# SAMC21_Xplained_Pro_Level_Converters.net
KiCad netlist of a schematic drawn in Altium Designer
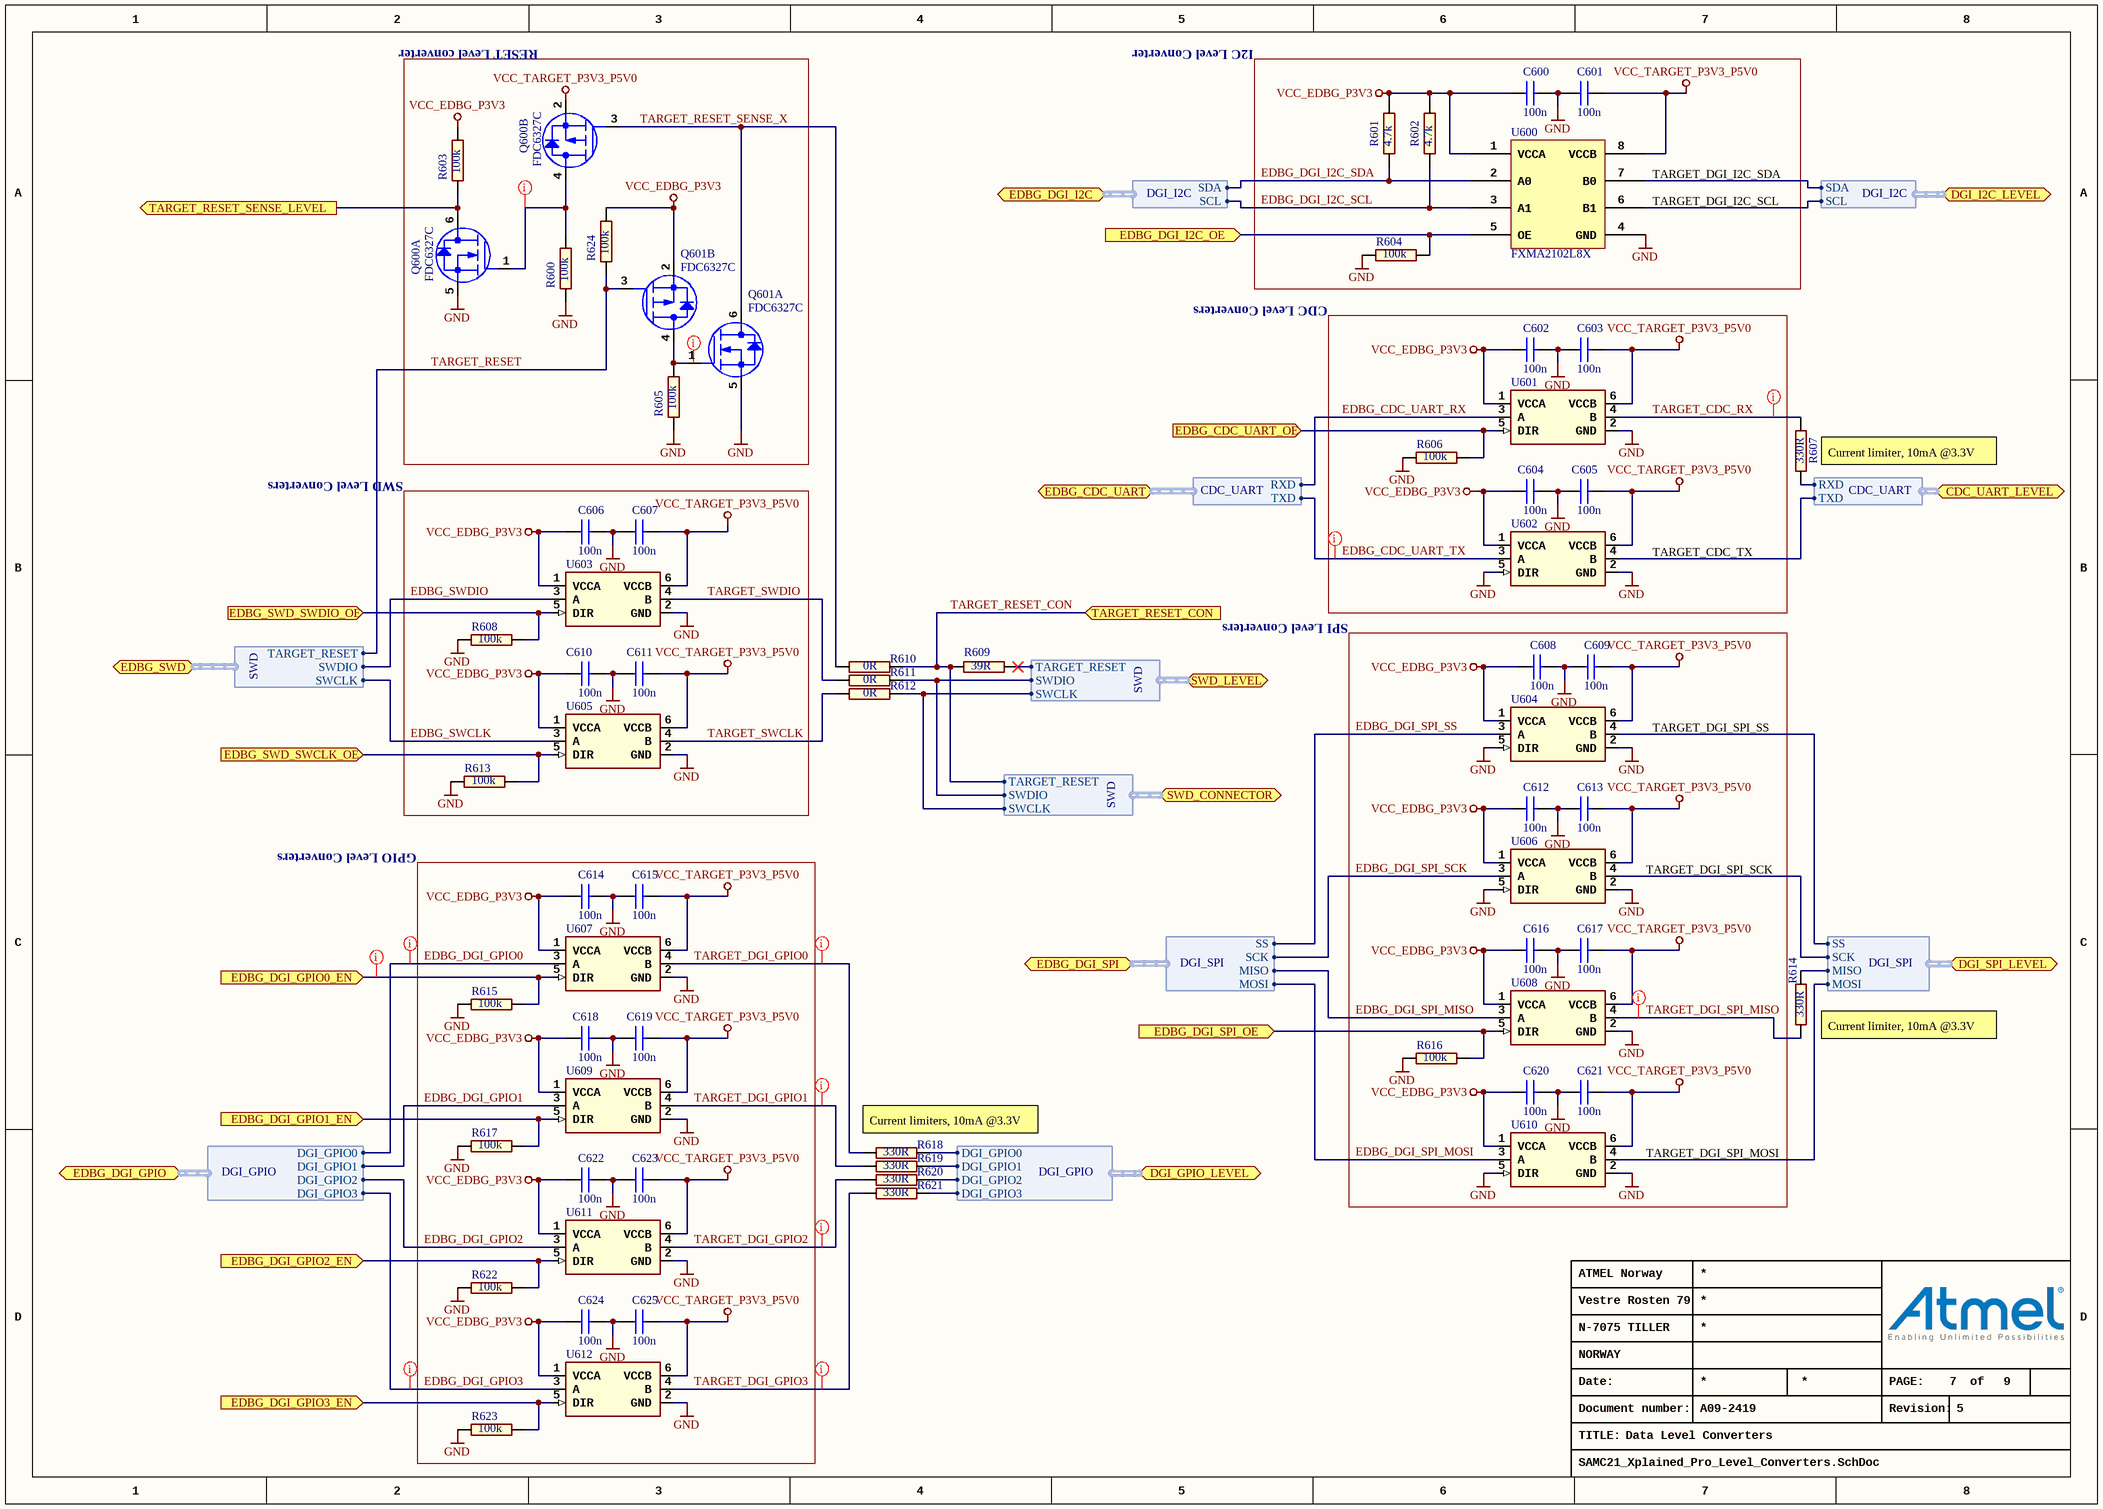
[diagram p0: SAMC21_Xplained_Pro_Level_Converters.SchDoc]

(export (version "E")
  (design (tool "Eeschema 10.0.6"))
  (components
    (comp (ref "C600")
      (value "100n")
      (footprint "AP1-00053")
      (description "Ceramic capacitor, SMD 0402, X7R, 16V, +/-10%")
      (fields (field (name "TOLERANCE") "16V, +/-10%") (field (name "MANUFACTURER") "Kemet"))
      (libsource (lib "AltiumDbLib") (part "CAP-NONPOL"))
    )
    (comp (ref "C601")
      (value "100n")
      (footprint "AP1-00053")
      (description "Ceramic capacitor, SMD 0402, X7R, 16V, +/-10%")
      (fields (field (name "TOLERANCE") "16V, +/-10%") (field (name "MANUFACTURER") "Kemet"))
      (libsource (lib "AltiumDbLib") (part "CAP-NONPOL"))
    )
    (comp (ref "C602")
      (value "100n")
      (footprint "AP1-00053")
      (description "Ceramic capacitor, SMD 0402, X7R, 16V, +/-10%")
      (fields (field (name "TOLERANCE") "16V, +/-10%") (field (name "MANUFACTURER") "Kemet"))
      (libsource (lib "AltiumDbLib") (part "CAP-NONPOL"))
    )
    (comp (ref "C603")
      (value "100n")
      (footprint "AP1-00053")
      (description "Ceramic capacitor, SMD 0402, X7R, 16V, +/-10%")
      (fields (field (name "TOLERANCE") "16V, +/-10%") (field (name "MANUFACTURER") "Kemet"))
      (libsource (lib "AltiumDbLib") (part "CAP-NONPOL"))
    )
    (comp (ref "C604")
      (value "100n")
      (footprint "AP1-00053")
      (description "Ceramic capacitor, SMD 0402, X7R, 16V, +/-10%")
      (fields (field (name "TOLERANCE") "16V, +/-10%") (field (name "MANUFACTURER") "Kemet"))
      (libsource (lib "AltiumDbLib") (part "CAP-NONPOL"))
    )
    (comp (ref "C605")
      (value "100n")
      (footprint "AP1-00053")
      (description "Ceramic capacitor, SMD 0402, X7R, 16V, +/-10%")
      (fields (field (name "TOLERANCE") "16V, +/-10%") (field (name "MANUFACTURER") "Kemet"))
      (libsource (lib "AltiumDbLib") (part "CAP-NONPOL"))
    )
    (comp (ref "C606")
      (value "100n")
      (footprint "AP1-00053")
      (description "Ceramic capacitor, SMD 0402, X7R, 16V, +/-10%")
      (fields (field (name "TOLERANCE") "16V, +/-10%") (field (name "MANUFACTURER") "Kemet"))
      (libsource (lib "AltiumDbLib") (part "CAP-NONPOL"))
    )
    (comp (ref "C607")
      (value "100n")
      (footprint "AP1-00053")
      (description "Ceramic capacitor, SMD 0402, X7R, 16V, +/-10%")
      (fields (field (name "TOLERANCE") "16V, +/-10%") (field (name "MANUFACTURER") "Kemet"))
      (libsource (lib "AltiumDbLib") (part "CAP-NONPOL"))
    )
    (comp (ref "C608")
      (value "100n")
      (footprint "AP1-00053")
      (description "Ceramic capacitor, SMD 0402, X7R, 16V, +/-10%")
      (fields (field (name "TOLERANCE") "16V, +/-10%") (field (name "MANUFACTURER") "Kemet"))
      (libsource (lib "AltiumDbLib") (part "CAP-NONPOL"))
    )
    (comp (ref "C609")
      (value "100n")
      (footprint "AP1-00053")
      (description "Ceramic capacitor, SMD 0402, X7R, 16V, +/-10%")
      (fields (field (name "TOLERANCE") "16V, +/-10%") (field (name "MANUFACTURER") "Kemet"))
      (libsource (lib "AltiumDbLib") (part "CAP-NONPOL"))
    )
    (comp (ref "C610")
      (value "100n")
      (footprint "AP1-00053")
      (description "Ceramic capacitor, SMD 0402, X7R, 16V, +/-10%")
      (fields (field (name "TOLERANCE") "16V, +/-10%") (field (name "MANUFACTURER") "Kemet"))
      (libsource (lib "AltiumDbLib") (part "CAP-NONPOL"))
    )
    (comp (ref "C611")
      (value "100n")
      (footprint "AP1-00053")
      (description "Ceramic capacitor, SMD 0402, X7R, 16V, +/-10%")
      (fields (field (name "TOLERANCE") "16V, +/-10%") (field (name "MANUFACTURER") "Kemet"))
      (libsource (lib "AltiumDbLib") (part "CAP-NONPOL"))
    )
    (comp (ref "C612")
      (value "100n")
      (footprint "AP1-00053")
      (description "Ceramic capacitor, SMD 0402, X7R, 16V, +/-10%")
      (fields (field (name "TOLERANCE") "16V, +/-10%") (field (name "MANUFACTURER") "Kemet"))
      (libsource (lib "AltiumDbLib") (part "CAP-NONPOL"))
    )
    (comp (ref "C613")
      (value "100n")
      (footprint "AP1-00053")
      (description "Ceramic capacitor, SMD 0402, X7R, 16V, +/-10%")
      (fields (field (name "TOLERANCE") "16V, +/-10%") (field (name "MANUFACTURER") "Kemet"))
      (libsource (lib "AltiumDbLib") (part "CAP-NONPOL"))
    )
    (comp (ref "C614")
      (value "100n")
      (footprint "AP1-00053")
      (description "Ceramic capacitor, SMD 0402, X7R, 16V, +/-10%")
      (fields (field (name "TOLERANCE") "16V, +/-10%") (field (name "MANUFACTURER") "Kemet"))
      (libsource (lib "AltiumDbLib") (part "CAP-NONPOL"))
    )
    (comp (ref "C615")
      (value "100n")
      (footprint "AP1-00053")
      (description "Ceramic capacitor, SMD 0402, X7R, 16V, +/-10%")
      (fields (field (name "TOLERANCE") "16V, +/-10%") (field (name "MANUFACTURER") "Kemet"))
      (libsource (lib "AltiumDbLib") (part "CAP-NONPOL"))
    )
    (comp (ref "C616")
      (value "100n")
      (footprint "AP1-00053")
      (description "Ceramic capacitor, SMD 0402, X7R, 16V, +/-10%")
      (fields (field (name "TOLERANCE") "16V, +/-10%") (field (name "MANUFACTURER") "Kemet"))
      (libsource (lib "AltiumDbLib") (part "CAP-NONPOL"))
    )
    (comp (ref "C617")
      (value "100n")
      (footprint "AP1-00053")
      (description "Ceramic capacitor, SMD 0402, X7R, 16V, +/-10%")
      (fields (field (name "TOLERANCE") "16V, +/-10%") (field (name "MANUFACTURER") "Kemet"))
      (libsource (lib "AltiumDbLib") (part "CAP-NONPOL"))
    )
    (comp (ref "C618")
      (value "100n")
      (footprint "AP1-00053")
      (description "Ceramic capacitor, SMD 0402, X7R, 16V, +/-10%")
      (fields (field (name "TOLERANCE") "16V, +/-10%") (field (name "MANUFACTURER") "Kemet"))
      (libsource (lib "AltiumDbLib") (part "CAP-NONPOL"))
    )
    (comp (ref "C619")
      (value "100n")
      (footprint "AP1-00053")
      (description "Ceramic capacitor, SMD 0402, X7R, 16V, +/-10%")
      (fields (field (name "TOLERANCE") "16V, +/-10%") (field (name "MANUFACTURER") "Kemet"))
      (libsource (lib "AltiumDbLib") (part "CAP-NONPOL"))
    )
    (comp (ref "C620")
      (value "100n")
      (footprint "AP1-00053")
      (description "Ceramic capacitor, SMD 0402, X7R, 16V, +/-10%")
      (fields (field (name "TOLERANCE") "16V, +/-10%") (field (name "MANUFACTURER") "Kemet"))
      (libsource (lib "AltiumDbLib") (part "CAP-NONPOL"))
    )
    (comp (ref "C621")
      (value "100n")
      (footprint "AP1-00053")
      (description "Ceramic capacitor, SMD 0402, X7R, 16V, +/-10%")
      (fields (field (name "TOLERANCE") "16V, +/-10%") (field (name "MANUFACTURER") "Kemet"))
      (libsource (lib "AltiumDbLib") (part "CAP-NONPOL"))
    )
    (comp (ref "C622")
      (value "100n")
      (footprint "AP1-00053")
      (description "Ceramic capacitor, SMD 0402, X7R, 16V, +/-10%")
      (fields (field (name "TOLERANCE") "16V, +/-10%") (field (name "MANUFACTURER") "Kemet"))
      (libsource (lib "AltiumDbLib") (part "CAP-NONPOL"))
    )
    (comp (ref "C623")
      (value "100n")
      (footprint "AP1-00053")
      (description "Ceramic capacitor, SMD 0402, X7R, 16V, +/-10%")
      (fields (field (name "TOLERANCE") "16V, +/-10%") (field (name "MANUFACTURER") "Kemet"))
      (libsource (lib "AltiumDbLib") (part "CAP-NONPOL"))
    )
    (comp (ref "C624")
      (value "100n")
      (footprint "AP1-00053")
      (description "Ceramic capacitor, SMD 0402, X7R, 16V, +/-10%")
      (fields (field (name "TOLERANCE") "16V, +/-10%") (field (name "MANUFACTURER") "Kemet"))
      (libsource (lib "AltiumDbLib") (part "CAP-NONPOL"))
    )
    (comp (ref "C625")
      (value "100n")
      (footprint "AP1-00053")
      (description "Ceramic capacitor, SMD 0402, X7R, 16V, +/-10%")
      (fields (field (name "TOLERANCE") "16V, +/-10%") (field (name "MANUFACTURER") "Kemet"))
      (libsource (lib "AltiumDbLib") (part "CAP-NONPOL"))
    )
    (comp (ref "Q600")
      (value "FDC6327C")
      (footprint "AP5-00008")
      (fields (field (name "MANUFACTURER") "Fairchild") (field (name "Comment") "Farnell no: 9844856"))
      (libsource (lib "AltiumDbLib") (part "DUAL_NP_G1S2G2D2S1D1"))
    )
    (comp (ref "Q601")
      (value "FDC6327C")
      (footprint "AP5-00008")
      (fields (field (name "MANUFACTURER") "Fairchild") (field (name "Comment") "Farnell no: 9844856"))
      (libsource (lib "AltiumDbLib") (part "DUAL_NP_G1S2G2D2S1D1"))
    )
    (comp (ref "R600")
      (value "100k")
      (footprint "AP2-00011")
      (description "Thick film resistor, SMD 0402, 1/16W, 1%")
      (fields (field (name "TOLERANCE") "1 %"))
      (libsource (lib "AltiumDbLib") (part "R2"))
    )
    (comp (ref "R601")
      (value "4.7k")
      (footprint "AP2-00011")
      (description "Thick film resistor, SMD 0402, 1/16W, 1%")
      (fields (field (name "TOLERANCE") "1 %"))
      (libsource (lib "AltiumDbLib") (part "R2"))
    )
    (comp (ref "R602")
      (value "4.7k")
      (footprint "AP2-00011")
      (description "Thick film resistor, SMD 0402, 1/16W, 1%")
      (fields (field (name "TOLERANCE") "1 %"))
      (libsource (lib "AltiumDbLib") (part "R2"))
    )
    (comp (ref "R603")
      (value "100k")
      (footprint "AP2-00011")
      (description "Thick film resistor, SMD 0402, 1/16W, 1%")
      (fields (field (name "TOLERANCE") "1 %"))
      (libsource (lib "AltiumDbLib") (part "R2"))
    )
    (comp (ref "R604")
      (value "100k")
      (footprint "AP2-00011")
      (description "Thick film resistor, SMD 0402, 1/16W, 1%")
      (fields (field (name "TOLERANCE") "1 %"))
      (libsource (lib "") (part "R2_2"))
    )
    (comp (ref "R605")
      (value "100k")
      (footprint "AP2-00011")
      (description "Thick film resistor, SMD 0402, 1/16W, 1%")
      (fields (field (name "TOLERANCE") "1 %"))
      (libsource (lib "AltiumDbLib") (part "R2"))
    )
    (comp (ref "R606")
      (value "100k")
      (footprint "AP2-00011")
      (description "Thick film resistor, SMD 0402, 1/16W, 1%")
      (fields (field (name "TOLERANCE") "1 %"))
      (libsource (lib "") (part "R2_1"))
    )
    (comp (ref "R607")
      (value "330R")
      (footprint "AP2-00011")
      (description "Thick film resistor, SMD 0402, 1/16W, 1%")
      (fields (field (name "TOLERANCE") "1 %"))
      (libsource (lib "AltiumDbLib") (part "R2"))
    )
    (comp (ref "R608")
      (value "100k")
      (footprint "AP2-00011")
      (description "Thick film resistor, SMD 0402, 1/16W, 1%")
      (fields (field (name "TOLERANCE") "1 %"))
      (libsource (lib "") (part "R2_1"))
    )
    (comp (ref "R609")
      (value "39R")
      (footprint "AP2-00011")
      (description "Thick film resistor, SMD 0402, 1/16W, 1%")
      (fields (field (name "TOLERANCE") "1 %"))
      (libsource (lib "") (part "R2_3"))
    )
    (comp (ref "R610")
      (value "0R")
      (footprint "AP2-00000")
      (description "Thick film resistor, SMD 0402, 1/16W, 1%")
      (fields (field (name "TOLERANCE") "1 %") (field (name "MANUFACTURER") "(n/a)"))
      (libsource (lib "") (part "R2_2"))
    )
    (comp (ref "R611")
      (value "0R")
      (footprint "AP2-00000")
      (description "Thick film resistor, SMD 0402, 1/16W, 1%")
      (fields (field (name "TOLERANCE") "1 %") (field (name "MANUFACTURER") "(n/a)"))
      (libsource (lib "") (part "R2_2"))
    )
    (comp (ref "R612")
      (value "0R")
      (footprint "AP2-00000")
      (description "Thick film resistor, SMD 0402, 1/16W, 1%")
      (fields (field (name "TOLERANCE") "1 %") (field (name "MANUFACTURER") "(n/a)"))
      (libsource (lib "") (part "R2_2"))
    )
    (comp (ref "R613")
      (value "100k")
      (footprint "AP2-00011")
      (description "Thick film resistor, SMD 0402, 1/16W, 1%")
      (fields (field (name "TOLERANCE") "1 %"))
      (libsource (lib "") (part "R2_1"))
    )
    (comp (ref "R614")
      (value "330R")
      (footprint "AP2-00011")
      (description "Thick film resistor, SMD 0402, 1/16W, 1%")
      (fields (field (name "TOLERANCE") "1 %"))
      (libsource (lib "AltiumDbLib") (part "R2"))
    )
    (comp (ref "R615")
      (value "100k")
      (footprint "AP2-00011")
      (description "Thick film resistor, SMD 0402, 1/16W, 1%")
      (fields (field (name "TOLERANCE") "1 %"))
      (libsource (lib "") (part "R2_1"))
    )
    (comp (ref "R616")
      (value "100k")
      (footprint "AP2-00011")
      (description "Thick film resistor, SMD 0402, 1/16W, 1%")
      (fields (field (name "TOLERANCE") "1 %"))
      (libsource (lib "") (part "R2_1"))
    )
    (comp (ref "R617")
      (value "100k")
      (footprint "AP2-00011")
      (description "Thick film resistor, SMD 0402, 1/16W, 1%")
      (fields (field (name "TOLERANCE") "1 %"))
      (libsource (lib "") (part "R2_1"))
    )
    (comp (ref "R618")
      (value "330R")
      (footprint "AP2-00011")
      (description "Thick film resistor, SMD 0402, 1/16W, 1%")
      (fields (field (name "TOLERANCE") "1 %"))
      (libsource (lib "") (part "R2_2"))
    )
    (comp (ref "R619")
      (value "330R")
      (footprint "AP2-00011")
      (description "Thick film resistor, SMD 0402, 1/16W, 1%")
      (fields (field (name "TOLERANCE") "1 %"))
      (libsource (lib "") (part "R2_2"))
    )
    (comp (ref "R620")
      (value "330R")
      (footprint "AP2-00011")
      (description "Thick film resistor, SMD 0402, 1/16W, 1%")
      (fields (field (name "TOLERANCE") "1 %"))
      (libsource (lib "") (part "R2_2"))
    )
    (comp (ref "R621")
      (value "330R")
      (footprint "AP2-00011")
      (description "Thick film resistor, SMD 0402, 1/16W, 1%")
      (fields (field (name "TOLERANCE") "1 %"))
      (libsource (lib "") (part "R2_2"))
    )
    (comp (ref "R622")
      (value "100k")
      (footprint "AP2-00011")
      (description "Thick film resistor, SMD 0402, 1/16W, 1%")
      (fields (field (name "TOLERANCE") "1 %"))
      (libsource (lib "") (part "R2_1"))
    )
    (comp (ref "R623")
      (value "100k")
      (footprint "AP2-00011")
      (description "Thick film resistor, SMD 0402, 1/16W, 1%")
      (fields (field (name "TOLERANCE") "1 %"))
      (libsource (lib "") (part "R2_1"))
    )
    (comp (ref "R624")
      (value "100k")
      (footprint "AP2-00011")
      (description "Thick film resistor, SMD 0402, 1/16W, 1%")
      (fields (field (name "TOLERANCE") "1 %"))
      (libsource (lib "AltiumDbLib") (part "R2"))
    )
    (comp (ref "U600")
      (value "FXMA2102L8X")
      (footprint "AP6-00258")
      (description "Dual supply, 2-bit, voltage translator, buffer, repeater, isolator for I2C applications")
      (fields (field (name "MANUFACTURER") "Fairchild"))
      (libsource (lib "AltiumDbLib") (part "FXMA2102"))
    )
    (comp (ref "U601")
      (value "~")
      (footprint "AP6-00015")
      (description "Single-Bit Dual-Supply Bus Transceiver with Configurable Voltage Translation and 3-State Outputs")
      (fields (field (name "MANUFACTURER") "Texas Instruments") (field (name "MPN") "SN74LVC1T45DCKR"))
      (libsource (lib "AltiumDbLib") (part "SN74LVC1T45DCKR"))
    )
    (comp (ref "U602")
      (value "~")
      (footprint "AP6-00015")
      (description "Single-Bit Dual-Supply Bus Transceiver with Configurable Voltage Translation and 3-State Outputs")
      (fields (field (name "MANUFACTURER") "Texas Instruments") (field (name "MPN") "SN74LVC1T45DCKR"))
      (libsource (lib "AltiumDbLib") (part "SN74LVC1T45DCKR"))
    )
    (comp (ref "U603")
      (value "~")
      (footprint "AP6-00015")
      (description "Single-Bit Dual-Supply Bus Transceiver with Configurable Voltage Translation and 3-State Outputs")
      (fields (field (name "MANUFACTURER") "Texas Instruments") (field (name "MPN") "SN74LVC1T45DCKR"))
      (libsource (lib "AltiumDbLib") (part "SN74LVC1T45DCKR"))
    )
    (comp (ref "U604")
      (value "~")
      (footprint "AP6-00015")
      (description "Single-Bit Dual-Supply Bus Transceiver with Configurable Voltage Translation and 3-State Outputs")
      (fields (field (name "MANUFACTURER") "Texas Instruments") (field (name "MPN") "SN74LVC1T45DCKR"))
      (libsource (lib "AltiumDbLib") (part "SN74LVC1T45DCKR"))
    )
    (comp (ref "U605")
      (value "~")
      (footprint "AP6-00015")
      (description "Single-Bit Dual-Supply Bus Transceiver with Configurable Voltage Translation and 3-State Outputs")
      (fields (field (name "MANUFACTURER") "Texas Instruments") (field (name "MPN") "SN74LVC1T45DCKR"))
      (libsource (lib "AltiumDbLib") (part "SN74LVC1T45DCKR"))
    )
    (comp (ref "U606")
      (value "~")
      (footprint "AP6-00015")
      (description "Single-Bit Dual-Supply Bus Transceiver with Configurable Voltage Translation and 3-State Outputs")
      (fields (field (name "MANUFACTURER") "Texas Instruments") (field (name "MPN") "SN74LVC1T45DCKR"))
      (libsource (lib "AltiumDbLib") (part "SN74LVC1T45DCKR"))
    )
    (comp (ref "U607")
      (value "~")
      (footprint "AP6-00015")
      (description "Single-Bit Dual-Supply Bus Transceiver with Configurable Voltage Translation and 3-State Outputs")
      (fields (field (name "MANUFACTURER") "Texas Instruments") (field (name "MPN") "SN74LVC1T45DCKR"))
      (libsource (lib "AltiumDbLib") (part "SN74LVC1T45DCKR"))
    )
    (comp (ref "U608")
      (value "~")
      (footprint "AP6-00015")
      (description "Single-Bit Dual-Supply Bus Transceiver with Configurable Voltage Translation and 3-State Outputs")
      (fields (field (name "MANUFACTURER") "Texas Instruments") (field (name "MPN") "SN74LVC1T45DCKR"))
      (libsource (lib "AltiumDbLib") (part "SN74LVC1T45DCKR"))
    )
    (comp (ref "U609")
      (value "~")
      (footprint "AP6-00015")
      (description "Single-Bit Dual-Supply Bus Transceiver with Configurable Voltage Translation and 3-State Outputs")
      (fields (field (name "MANUFACTURER") "Texas Instruments") (field (name "MPN") "SN74LVC1T45DCKR"))
      (libsource (lib "AltiumDbLib") (part "SN74LVC1T45DCKR"))
    )
    (comp (ref "U610")
      (value "~")
      (footprint "AP6-00015")
      (description "Single-Bit Dual-Supply Bus Transceiver with Configurable Voltage Translation and 3-State Outputs")
      (fields (field (name "MANUFACTURER") "Texas Instruments") (field (name "MPN") "SN74LVC1T45DCKR"))
      (libsource (lib "AltiumDbLib") (part "SN74LVC1T45DCKR"))
    )
    (comp (ref "U611")
      (value "~")
      (footprint "AP6-00015")
      (description "Single-Bit Dual-Supply Bus Transceiver with Configurable Voltage Translation and 3-State Outputs")
      (fields (field (name "MANUFACTURER") "Texas Instruments") (field (name "MPN") "SN74LVC1T45DCKR"))
      (libsource (lib "AltiumDbLib") (part "SN74LVC1T45DCKR"))
    )
    (comp (ref "U612")
      (value "~")
      (footprint "AP6-00015")
      (description "Single-Bit Dual-Supply Bus Transceiver with Configurable Voltage Translation and 3-State Outputs")
      (fields (field (name "MANUFACTURER") "Texas Instruments") (field (name "MPN") "SN74LVC1T45DCKR"))
      (libsource (lib "AltiumDbLib") (part "SN74LVC1T45DCKR"))
    )
  )
  (nets
    (net (code "6") (name "/EDBG_CDC_UART_OE") (class "Default")
      (node (ref "R606") (pin "1") (pinfunction "1_1") (pintype "passive"))
      (node (ref "U601") (pin "5") (pinfunction "DIR_5") (pintype "input"))
    )
    (net (code "7") (name "/EDBG_CDC_UART_RX") (class "Default")
      (node (ref "U601") (pin "3") (pinfunction "A_3") (pintype "bidirectional"))
    )
    (net (code "8") (name "/EDBG_CDC_UART_TX") (class "Default")
      (node (ref "U602") (pin "3") (pinfunction "A_3") (pintype "bidirectional"))
    )
    (net (code "9") (name "/EDBG_DGI_GPIO0") (class "Default")
      (node (ref "U607") (pin "3") (pinfunction "A_3") (pintype "bidirectional"))
    )
    (net (code "10") (name "/EDBG_DGI_GPIO0_EN") (class "Default")
      (node (ref "R615") (pin "1") (pinfunction "1_1") (pintype "passive"))
      (node (ref "U607") (pin "5") (pinfunction "DIR_5") (pintype "input"))
    )
    (net (code "11") (name "/EDBG_DGI_GPIO1") (class "Default")
      (node (ref "U609") (pin "3") (pinfunction "A_3") (pintype "bidirectional"))
    )
    (net (code "12") (name "/EDBG_DGI_GPIO1_EN") (class "Default")
      (node (ref "R617") (pin "1") (pinfunction "1_1") (pintype "passive"))
      (node (ref "U609") (pin "5") (pinfunction "DIR_5") (pintype "input"))
    )
    (net (code "13") (name "/EDBG_DGI_GPIO2") (class "Default")
      (node (ref "U611") (pin "3") (pinfunction "A_3") (pintype "bidirectional"))
    )
    (net (code "14") (name "/EDBG_DGI_GPIO2_EN") (class "Default")
      (node (ref "R622") (pin "1") (pinfunction "1_1") (pintype "passive"))
      (node (ref "U611") (pin "5") (pinfunction "DIR_5") (pintype "input"))
    )
    (net (code "15") (name "/EDBG_DGI_GPIO3") (class "Default")
      (node (ref "U612") (pin "3") (pinfunction "A_3") (pintype "bidirectional"))
    )
    (net (code "16") (name "/EDBG_DGI_GPIO3_EN") (class "Default")
      (node (ref "R623") (pin "1") (pinfunction "1_1") (pintype "passive"))
      (node (ref "U612") (pin "5") (pinfunction "DIR_5") (pintype "input"))
    )
    (net (code "17") (name "/EDBG_DGI_I2C_OE") (class "Default")
      (node (ref "R604") (pin "2") (pinfunction "2_2") (pintype "passive"))
      (node (ref "U600") (pin "5") (pinfunction "OE_5") (pintype "passive"))
    )
    (net (code "18") (name "/EDBG_DGI_I2C_SCL") (class "Default")
      (node (ref "R602") (pin "1") (pinfunction "1_1") (pintype "passive"))
      (node (ref "U600") (pin "3") (pinfunction "A1_3") (pintype "open_collector"))
    )
    (net (code "19") (name "/EDBG_DGI_I2C_SDA") (class "Default")
      (node (ref "R601") (pin "1") (pinfunction "1_1") (pintype "passive"))
      (node (ref "U600") (pin "2") (pinfunction "A0_2") (pintype "open_collector"))
    )
    (net (code "20") (name "/EDBG_DGI_SPI_MISO") (class "Default")
      (node (ref "U608") (pin "3") (pinfunction "A_3") (pintype "bidirectional"))
    )
    (net (code "21") (name "/EDBG_DGI_SPI_MOSI") (class "Default")
      (node (ref "U610") (pin "3") (pinfunction "A_3") (pintype "bidirectional"))
    )
    (net (code "22") (name "/EDBG_DGI_SPI_OE") (class "Default")
      (node (ref "R616") (pin "1") (pinfunction "1_1") (pintype "passive"))
      (node (ref "U608") (pin "5") (pinfunction "DIR_5") (pintype "input"))
    )
    (net (code "23") (name "/EDBG_DGI_SPI_SCK") (class "Default")
      (node (ref "U606") (pin "3") (pinfunction "A_3") (pintype "bidirectional"))
    )
    (net (code "24") (name "/EDBG_DGI_SPI_SS") (class "Default")
      (node (ref "U604") (pin "3") (pinfunction "A_3") (pintype "bidirectional"))
    )
    (net (code "25") (name "/EDBG_SWCLK") (class "Default")
      (node (ref "U605") (pin "3") (pinfunction "A_3") (pintype "bidirectional"))
    )
    (net (code "26") (name "/EDBG_SWDIO") (class "Default")
      (node (ref "U603") (pin "3") (pinfunction "A_3") (pintype "bidirectional"))
    )
    (net (code "27") (name "/EDBG_SWD_SWCLK_OE") (class "Default")
      (node (ref "R613") (pin "1") (pinfunction "1_1") (pintype "passive"))
      (node (ref "U605") (pin "5") (pinfunction "DIR_5") (pintype "input"))
    )
    (net (code "28") (name "/EDBG_SWD_SWDIO_OE") (class "Default")
      (node (ref "R608") (pin "1") (pinfunction "1_1") (pintype "passive"))
      (node (ref "U603") (pin "5") (pinfunction "DIR_5") (pintype "input"))
    )
    (net (code "29") (name "/TARGET_CDC_RX") (class "Default")
      (node (ref "R607") (pin "2") (pinfunction "2_2") (pintype "passive"))
      (node (ref "U601") (pin "4") (pinfunction "B_4") (pintype "bidirectional"))
    )
    (net (code "30") (name "/TARGET_DGI_GPIO0") (class "Default")
      (node (ref "R618") (pin "1") (pinfunction "1_1") (pintype "passive"))
      (node (ref "U607") (pin "4") (pinfunction "B_4") (pintype "bidirectional"))
    )
    (net (code "31") (name "/TARGET_DGI_GPIO1") (class "Default")
      (node (ref "R619") (pin "1") (pinfunction "1_1") (pintype "passive"))
      (node (ref "U609") (pin "4") (pinfunction "B_4") (pintype "bidirectional"))
    )
    (net (code "32") (name "/TARGET_DGI_GPIO2") (class "Default")
      (node (ref "R620") (pin "1") (pinfunction "1_1") (pintype "passive"))
      (node (ref "U611") (pin "4") (pinfunction "B_4") (pintype "bidirectional"))
    )
    (net (code "33") (name "/TARGET_DGI_GPIO3") (class "Default")
      (node (ref "R621") (pin "1") (pinfunction "1_1") (pintype "passive"))
      (node (ref "U612") (pin "4") (pinfunction "B_4") (pintype "bidirectional"))
    )
    (net (code "34") (name "/TARGET_DGI_SPI_MISO") (class "Default")
      (node (ref "R614") (pin "1") (pinfunction "1_1") (pintype "passive"))
      (node (ref "U608") (pin "4") (pinfunction "B_4") (pintype "bidirectional"))
    )
    (net (code "35") (name "/TARGET_RESET") (class "Default")
      (node (ref "Q601") (pin "3") (pinfunction "G_3") (pintype "passive"))
      (node (ref "R624") (pin "1") (pinfunction "1_1") (pintype "passive"))
    )
    (net (code "36") (name "/TARGET_RESET_CON") (class "Default")
      (node (ref "R609") (pin "1") (pinfunction "1_1") (pintype "passive"))
      (node (ref "R610") (pin "2") (pinfunction "2_2") (pintype "passive"))
    )
    (net (code "37") (name "/TARGET_RESET_SENSE_LEVEL") (class "Default")
      (node (ref "Q600") (pin "6") (pinfunction "D_6") (pintype "passive"))
      (node (ref "R603") (pin "1") (pinfunction "1_1") (pintype "passive"))
    )
    (net (code "38") (name "/TARGET_RESET_SENSE_X") (class "Default")
      (node (ref "Q600") (pin "3") (pinfunction "G_3") (pintype "passive"))
      (node (ref "Q601") (pin "6") (pinfunction "D_6") (pintype "passive"))
      (node (ref "R610") (pin "1") (pinfunction "1_1") (pintype "passive"))
    )
    (net (code "39") (name "/TARGET_SWCLK") (class "Default")
      (node (ref "R612") (pin "1") (pinfunction "1_1") (pintype "passive"))
      (node (ref "U605") (pin "4") (pinfunction "B_4") (pintype "bidirectional"))
    )
    (net (code "40") (name "/TARGET_SWDIO") (class "Default")
      (node (ref "R611") (pin "1") (pinfunction "1_1") (pintype "passive"))
      (node (ref "U603") (pin "4") (pinfunction "B_4") (pintype "bidirectional"))
    )
    (net (code "46") (name "GND") (class "Default")
      (node (ref "C600") (pin "2") (pinfunction "2_2") (pintype "passive"))
      (node (ref "C601") (pin "1") (pinfunction "1_1") (pintype "passive"))
      (node (ref "C602") (pin "2") (pinfunction "2_2") (pintype "passive"))
      (node (ref "C603") (pin "1") (pinfunction "1_1") (pintype "passive"))
      (node (ref "C604") (pin "2") (pinfunction "2_2") (pintype "passive"))
      (node (ref "C605") (pin "1") (pinfunction "1_1") (pintype "passive"))
      (node (ref "C606") (pin "2") (pinfunction "2_2") (pintype "passive"))
      (node (ref "C607") (pin "1") (pinfunction "1_1") (pintype "passive"))
      (node (ref "C608") (pin "2") (pinfunction "2_2") (pintype "passive"))
      (node (ref "C609") (pin "1") (pinfunction "1_1") (pintype "passive"))
      (node (ref "C610") (pin "2") (pinfunction "2_2") (pintype "passive"))
      (node (ref "C611") (pin "1") (pinfunction "1_1") (pintype "passive"))
      (node (ref "C612") (pin "2") (pinfunction "2_2") (pintype "passive"))
      (node (ref "C613") (pin "1") (pinfunction "1_1") (pintype "passive"))
      (node (ref "C614") (pin "2") (pinfunction "2_2") (pintype "passive"))
      (node (ref "C615") (pin "1") (pinfunction "1_1") (pintype "passive"))
      (node (ref "C616") (pin "2") (pinfunction "2_2") (pintype "passive"))
      (node (ref "C617") (pin "1") (pinfunction "1_1") (pintype "passive"))
      (node (ref "C618") (pin "2") (pinfunction "2_2") (pintype "passive"))
      (node (ref "C619") (pin "1") (pinfunction "1_1") (pintype "passive"))
      (node (ref "C620") (pin "2") (pinfunction "2_2") (pintype "passive"))
      (node (ref "C621") (pin "1") (pinfunction "1_1") (pintype "passive"))
      (node (ref "C622") (pin "2") (pinfunction "2_2") (pintype "passive"))
      (node (ref "C623") (pin "1") (pinfunction "1_1") (pintype "passive"))
      (node (ref "C624") (pin "2") (pinfunction "2_2") (pintype "passive"))
      (node (ref "C625") (pin "1") (pinfunction "1_1") (pintype "passive"))
      (node (ref "Q600") (pin "5") (pinfunction "S_5") (pintype "passive"))
      (node (ref "Q601") (pin "5") (pinfunction "S_5") (pintype "passive"))
      (node (ref "R600") (pin "1") (pinfunction "1_1") (pintype "passive"))
      (node (ref "R604") (pin "1") (pinfunction "1_1") (pintype "passive"))
      (node (ref "R605") (pin "1") (pinfunction "1_1") (pintype "passive"))
      (node (ref "R606") (pin "2") (pinfunction "2_2") (pintype "passive"))
      (node (ref "R608") (pin "2") (pinfunction "2_2") (pintype "passive"))
      (node (ref "R613") (pin "2") (pinfunction "2_2") (pintype "passive"))
      (node (ref "R615") (pin "2") (pinfunction "2_2") (pintype "passive"))
      (node (ref "R616") (pin "2") (pinfunction "2_2") (pintype "passive"))
      (node (ref "R617") (pin "2") (pinfunction "2_2") (pintype "passive"))
      (node (ref "R622") (pin "2") (pinfunction "2_2") (pintype "passive"))
      (node (ref "R623") (pin "2") (pinfunction "2_2") (pintype "passive"))
      (node (ref "U600") (pin "4") (pinfunction "GND_4") (pintype "power_in"))
      (node (ref "U601") (pin "2") (pinfunction "GND_2") (pintype "power_in"))
      (node (ref "U602") (pin "2") (pinfunction "GND_2") (pintype "power_in"))
      (node (ref "U602") (pin "5") (pinfunction "DIR_5") (pintype "input"))
      (node (ref "U603") (pin "2") (pinfunction "GND_2") (pintype "power_in"))
      (node (ref "U604") (pin "2") (pinfunction "GND_2") (pintype "power_in"))
      (node (ref "U604") (pin "5") (pinfunction "DIR_5") (pintype "input"))
      (node (ref "U605") (pin "2") (pinfunction "GND_2") (pintype "power_in"))
      (node (ref "U606") (pin "2") (pinfunction "GND_2") (pintype "power_in"))
      (node (ref "U606") (pin "5") (pinfunction "DIR_5") (pintype "input"))
      (node (ref "U607") (pin "2") (pinfunction "GND_2") (pintype "power_in"))
      (node (ref "U608") (pin "2") (pinfunction "GND_2") (pintype "power_in"))
      (node (ref "U609") (pin "2") (pinfunction "GND_2") (pintype "power_in"))
      (node (ref "U610") (pin "2") (pinfunction "GND_2") (pintype "power_in"))
      (node (ref "U610") (pin "5") (pinfunction "DIR_5") (pintype "input"))
      (node (ref "U611") (pin "2") (pinfunction "GND_2") (pintype "power_in"))
      (node (ref "U612") (pin "2") (pinfunction "GND_2") (pintype "power_in"))
    )
    (net (code "47") (name "Net-(Q600A-G)") (class "Default")
      (node (ref "Q600") (pin "1") (pinfunction "G_1") (pintype "passive"))
      (node (ref "Q600") (pin "4") (pinfunction "D_4") (pintype "passive"))
      (node (ref "R600") (pin "2") (pinfunction "2_2") (pintype "passive"))
    )
    (net (code "48") (name "Net-(Q601A-G)") (class "Default")
      (node (ref "Q601") (pin "1") (pinfunction "G_1") (pintype "passive"))
      (node (ref "Q601") (pin "4") (pinfunction "D_4") (pintype "passive"))
      (node (ref "R605") (pin "2") (pinfunction "2_2") (pintype "passive"))
    )
    (net (code "49") (name "VCC_EDBG_P3V3") (class "Default")
      (node (ref "C600") (pin "1") (pinfunction "1_1") (pintype "passive"))
      (node (ref "C602") (pin "1") (pinfunction "1_1") (pintype "passive"))
      (node (ref "C604") (pin "1") (pinfunction "1_1") (pintype "passive"))
      (node (ref "C606") (pin "1") (pinfunction "1_1") (pintype "passive"))
      (node (ref "C608") (pin "1") (pinfunction "1_1") (pintype "passive"))
      (node (ref "C610") (pin "1") (pinfunction "1_1") (pintype "passive"))
      (node (ref "C612") (pin "1") (pinfunction "1_1") (pintype "passive"))
      (node (ref "C614") (pin "1") (pinfunction "1_1") (pintype "passive"))
      (node (ref "C616") (pin "1") (pinfunction "1_1") (pintype "passive"))
      (node (ref "C618") (pin "1") (pinfunction "1_1") (pintype "passive"))
      (node (ref "C620") (pin "1") (pinfunction "1_1") (pintype "passive"))
      (node (ref "C622") (pin "1") (pinfunction "1_1") (pintype "passive"))
      (node (ref "C624") (pin "1") (pinfunction "1_1") (pintype "passive"))
      (node (ref "Q601") (pin "2") (pinfunction "S_2") (pintype "passive"))
      (node (ref "R601") (pin "2") (pinfunction "2_2") (pintype "passive"))
      (node (ref "R602") (pin "2") (pinfunction "2_2") (pintype "passive"))
      (node (ref "R603") (pin "2") (pinfunction "2_2") (pintype "passive"))
      (node (ref "R624") (pin "2") (pinfunction "2_2") (pintype "passive"))
      (node (ref "U600") (pin "1") (pinfunction "VCCA_1") (pintype "power_in"))
      (node (ref "U601") (pin "1") (pinfunction "VCCA_1") (pintype "power_in"))
      (node (ref "U602") (pin "1") (pinfunction "VCCA_1") (pintype "power_in"))
      (node (ref "U603") (pin "1") (pinfunction "VCCA_1") (pintype "power_in"))
      (node (ref "U604") (pin "1") (pinfunction "VCCA_1") (pintype "power_in"))
      (node (ref "U605") (pin "1") (pinfunction "VCCA_1") (pintype "power_in"))
      (node (ref "U606") (pin "1") (pinfunction "VCCA_1") (pintype "power_in"))
      (node (ref "U607") (pin "1") (pinfunction "VCCA_1") (pintype "power_in"))
      (node (ref "U608") (pin "1") (pinfunction "VCCA_1") (pintype "power_in"))
      (node (ref "U609") (pin "1") (pinfunction "VCCA_1") (pintype "power_in"))
      (node (ref "U610") (pin "1") (pinfunction "VCCA_1") (pintype "power_in"))
      (node (ref "U611") (pin "1") (pinfunction "VCCA_1") (pintype "power_in"))
      (node (ref "U612") (pin "1") (pinfunction "VCCA_1") (pintype "power_in"))
    )
    (net (code "50") (name "VCC_TARGET_P3V3_P5V0") (class "Default")
      (node (ref "C601") (pin "2") (pinfunction "2_2") (pintype "passive"))
      (node (ref "C603") (pin "2") (pinfunction "2_2") (pintype "passive"))
      (node (ref "C605") (pin "2") (pinfunction "2_2") (pintype "passive"))
      (node (ref "C607") (pin "2") (pinfunction "2_2") (pintype "passive"))
      (node (ref "C609") (pin "2") (pinfunction "2_2") (pintype "passive"))
      (node (ref "C611") (pin "2") (pinfunction "2_2") (pintype "passive"))
      (node (ref "C613") (pin "2") (pinfunction "2_2") (pintype "passive"))
      (node (ref "C615") (pin "2") (pinfunction "2_2") (pintype "passive"))
      (node (ref "C617") (pin "2") (pinfunction "2_2") (pintype "passive"))
      (node (ref "C619") (pin "2") (pinfunction "2_2") (pintype "passive"))
      (node (ref "C621") (pin "2") (pinfunction "2_2") (pintype "passive"))
      (node (ref "C623") (pin "2") (pinfunction "2_2") (pintype "passive"))
      (node (ref "C625") (pin "2") (pinfunction "2_2") (pintype "passive"))
      (node (ref "Q600") (pin "2") (pinfunction "S_2") (pintype "passive"))
      (node (ref "U600") (pin "8") (pinfunction "VCCB_8") (pintype "power_in"))
      (node (ref "U601") (pin "6") (pinfunction "VCCB_6") (pintype "power_in"))
      (node (ref "U602") (pin "6") (pinfunction "VCCB_6") (pintype "power_in"))
      (node (ref "U603") (pin "6") (pinfunction "VCCB_6") (pintype "power_in"))
      (node (ref "U604") (pin "6") (pinfunction "VCCB_6") (pintype "power_in"))
      (node (ref "U605") (pin "6") (pinfunction "VCCB_6") (pintype "power_in"))
      (node (ref "U606") (pin "6") (pinfunction "VCCB_6") (pintype "power_in"))
      (node (ref "U607") (pin "6") (pinfunction "VCCB_6") (pintype "power_in"))
      (node (ref "U608") (pin "6") (pinfunction "VCCB_6") (pintype "power_in"))
      (node (ref "U609") (pin "6") (pinfunction "VCCB_6") (pintype "power_in"))
      (node (ref "U610") (pin "6") (pinfunction "VCCB_6") (pintype "power_in"))
      (node (ref "U611") (pin "6") (pinfunction "VCCB_6") (pintype "power_in"))
      (node (ref "U612") (pin "6") (pinfunction "VCCB_6") (pintype "power_in"))
    )
    (net (code "51") (name "unconnected-(R607-Pad1)") (class "Default")
      (node (ref "R607") (pin "1") (pinfunction "1_1") (pintype "passive"))
    )
    (net (code "52") (name "unconnected-(R609-Pad2)") (class "Default")
      (node (ref "R609") (pin "2") (pinfunction "2_2") (pintype "passive+no_connect"))
    )
    (net (code "53") (name "unconnected-(R611-Pad2)") (class "Default")
      (node (ref "R611") (pin "2") (pinfunction "2_2") (pintype "passive"))
    )
    (net (code "54") (name "unconnected-(R612-Pad2)") (class "Default")
      (node (ref "R612") (pin "2") (pinfunction "2_2") (pintype "passive"))
    )
    (net (code "55") (name "unconnected-(R614-Pad2)") (class "Default")
      (node (ref "R614") (pin "2") (pinfunction "2_2") (pintype "passive"))
    )
    (net (code "56") (name "unconnected-(R618-Pad2)") (class "Default")
      (node (ref "R618") (pin "2") (pinfunction "2_2") (pintype "passive"))
    )
    (net (code "57") (name "unconnected-(R619-Pad2)") (class "Default")
      (node (ref "R619") (pin "2") (pinfunction "2_2") (pintype "passive"))
    )
    (net (code "58") (name "unconnected-(R620-Pad2)") (class "Default")
      (node (ref "R620") (pin "2") (pinfunction "2_2") (pintype "passive"))
    )
    (net (code "59") (name "unconnected-(R621-Pad2)") (class "Default")
      (node (ref "R621") (pin "2") (pinfunction "2_2") (pintype "passive"))
    )
    (net (code "60") (name "unconnected-(U600-B0-Pad7)") (class "Default")
      (node (ref "U600") (pin "7") (pinfunction "B0_7") (pintype "open_collector"))
    )
    (net (code "61") (name "unconnected-(U600-B1-Pad6)") (class "Default")
      (node (ref "U600") (pin "6") (pinfunction "B1_6") (pintype "open_collector"))
    )
    (net (code "62") (name "unconnected-(U602-B-Pad4)") (class "Default")
      (node (ref "U602") (pin "4") (pinfunction "B_4") (pintype "bidirectional"))
    )
    (net (code "63") (name "unconnected-(U604-B-Pad4)") (class "Default")
      (node (ref "U604") (pin "4") (pinfunction "B_4") (pintype "bidirectional"))
    )
    (net (code "64") (name "unconnected-(U606-B-Pad4)") (class "Default")
      (node (ref "U606") (pin "4") (pinfunction "B_4") (pintype "bidirectional"))
    )
    (net (code "65") (name "unconnected-(U610-B-Pad4)") (class "Default")
      (node (ref "U610") (pin "4") (pinfunction "B_4") (pintype "bidirectional"))
    )
  )
)
